# STM32F103CBT6-sphbot.net
KiCad netlist of a schematic drawn in Altium Designer
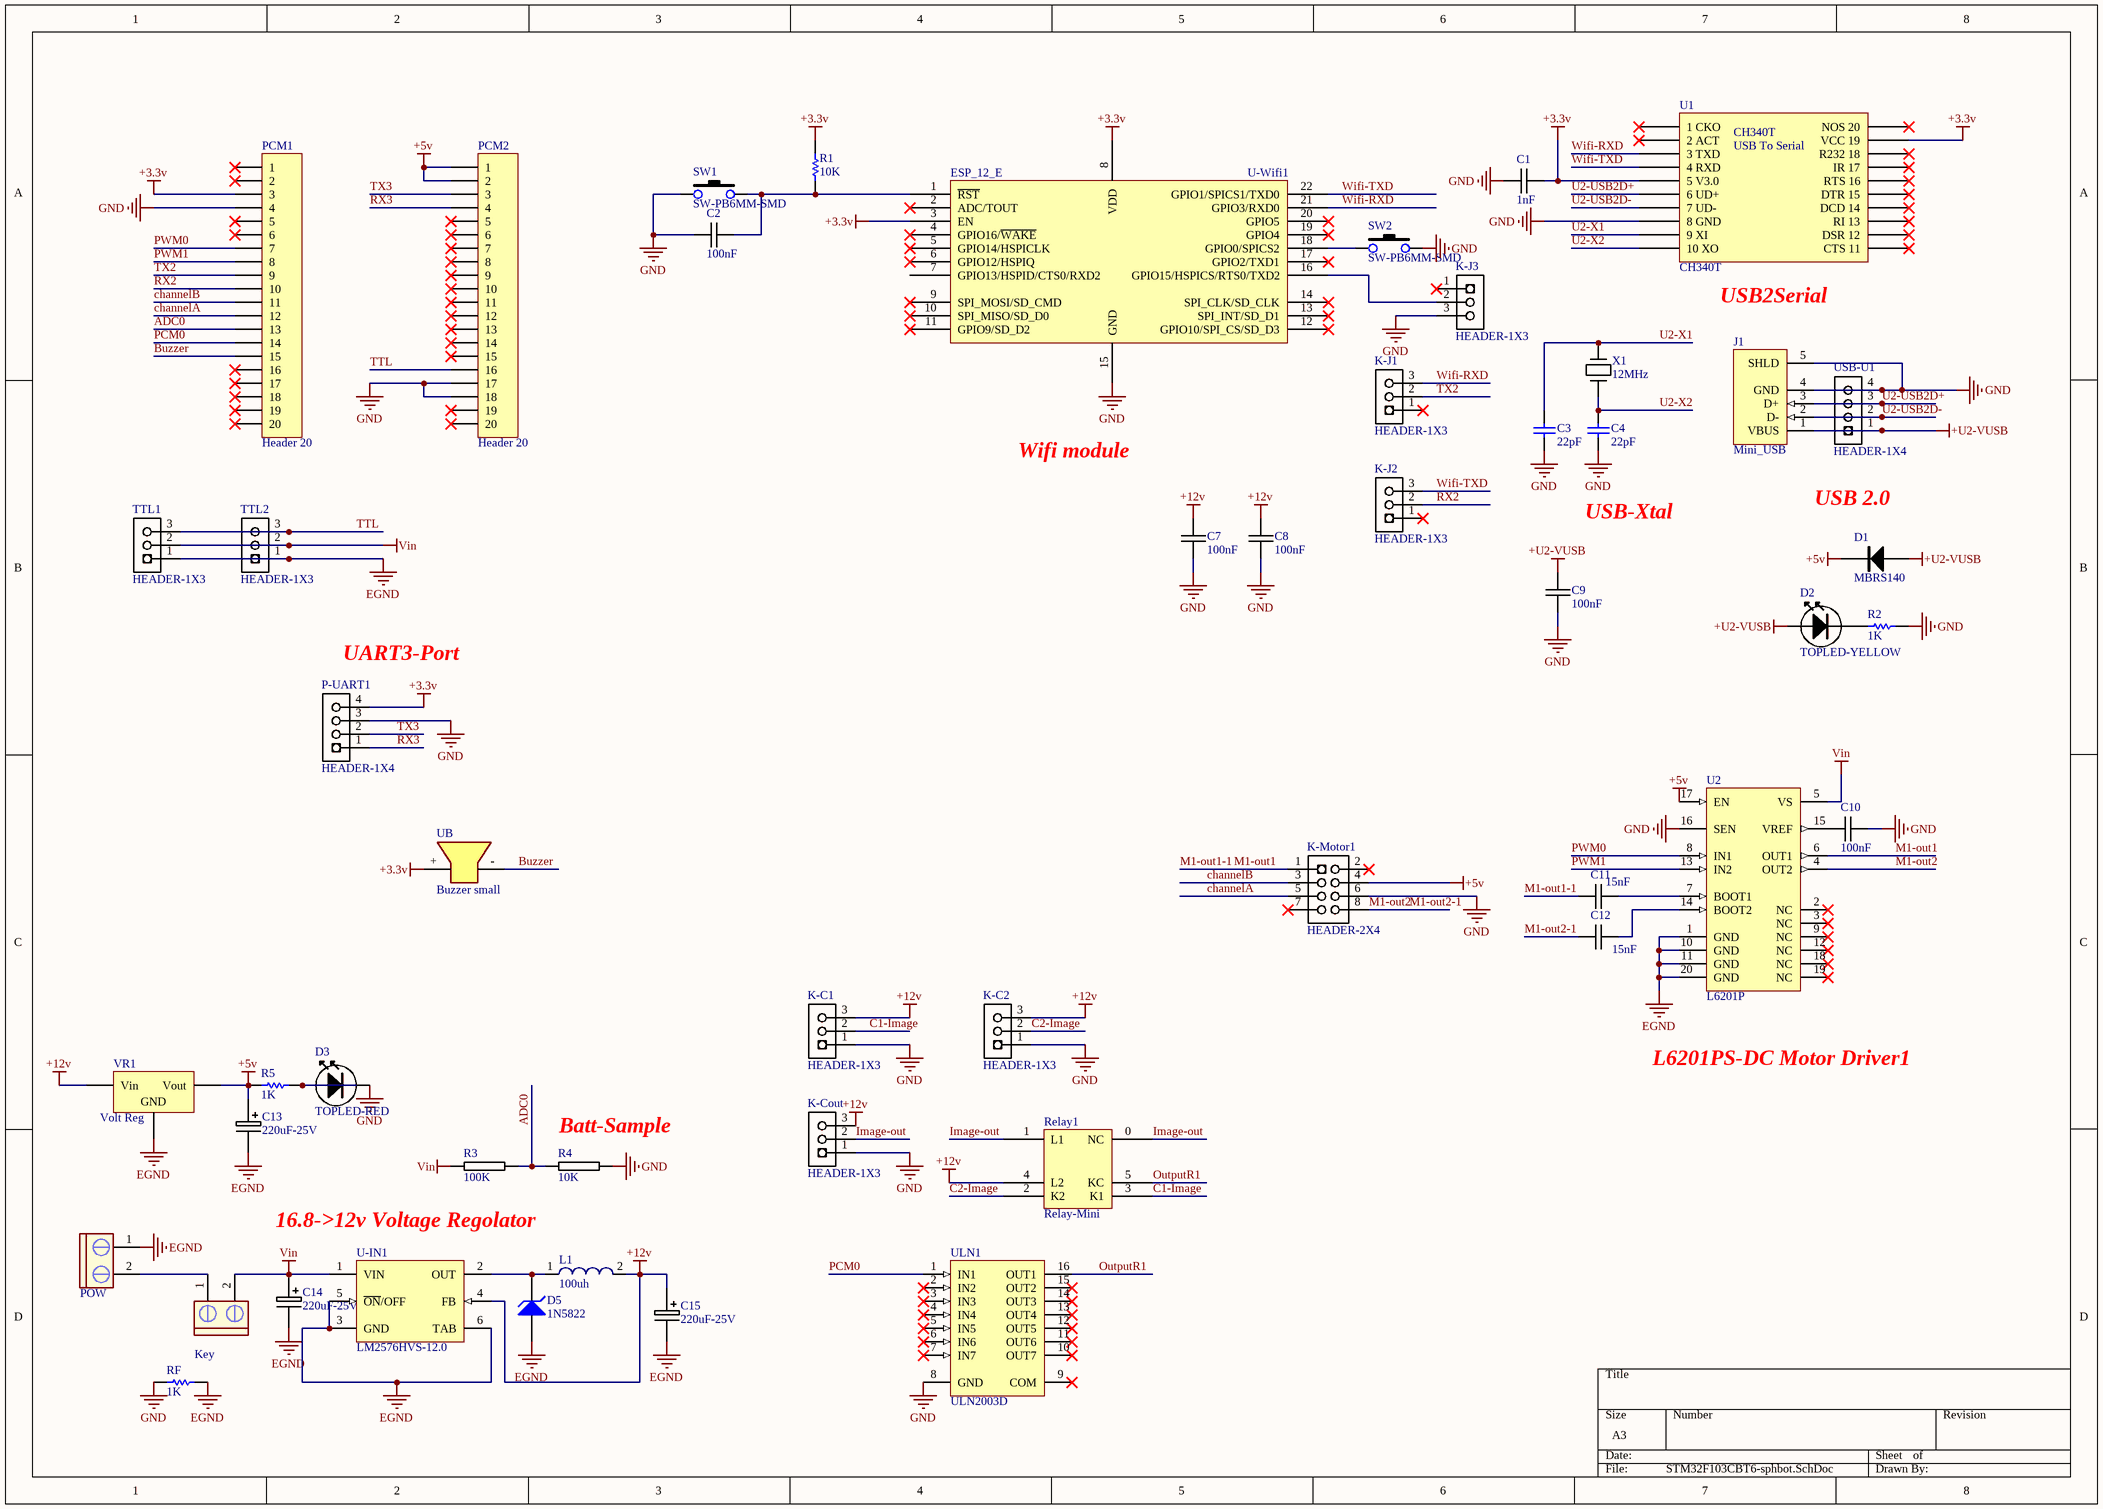
[diagram p0: STM32F103CBT6-sphbot.SchDoc]

(export (version "E")
  (design (tool "Eeschema 10.0.6"))
  (components
    (comp (ref "C1")
      (value "1nF")
      (footprint "0805C-TBD")
      (description "CAPACITOR 0805 CERAMIC")
      (libsource (lib "vh_altium_library") (part "0805C-18PF-50V-C0G-JOH"))
    )
    (comp (ref "C2")
      (value "100nF")
      (footprint "0805C-TBD")
      (description "CAPACITOR 0805 CERAMIC")
      (libsource (lib "vh_altium_library") (part "0805C-100nF-25V-X7R-MUR"))
    )
    (comp (ref "C3")
      (value "22pF")
      (footprint "0805C-TBD")
      (description "Capacitor (Semiconductor SIM Model)")
      (fields (field (name "PUBLISHER") "Altium Limited"))
      (libsource (lib "Miscellaneous Devices") (part "Cap Semi"))
    )
    (comp (ref "C4")
      (value "22pF")
      (footprint "0805C-TBD")
      (description "Capacitor (Semiconductor SIM Model)")
      (fields (field (name "PUBLISHER") "Altium Limited"))
      (libsource (lib "Miscellaneous Devices") (part "Cap Semi"))
    )
    (comp (ref "C7")
      (value "100nF")
      (footprint "0805C-TBD")
      (description "CAPACITOR 0805 CERAMIC")
      (libsource (lib "vh_altium_library") (part "0805C-100nF-25V-X7R-MUR"))
    )
    (comp (ref "C8")
      (value "100nF")
      (footprint "0805C-TBD")
      (description "CAPACITOR 0805 CERAMIC")
      (libsource (lib "vh_altium_library") (part "0805C-100nF-25V-X7R-MUR"))
    )
    (comp (ref "C9")
      (value "100nF")
      (footprint "0805C-TBD")
      (description "CAPACITOR 0805 CERAMIC")
      (libsource (lib "vh_altium_library") (part "0805C-100nF-25V-X7R-MUR"))
    )
    (comp (ref "C10")
      (value "100nF")
      (footprint "0805C-TBD")
      (description "CAPACITOR 0805 CERAMIC")
      (libsource (lib "vh_altium_library") (part "0805C-100nF-25V-X7R-MUR"))
    )
    (comp (ref "C11")
      (value "15nF")
      (footprint "0805C-TBD")
      (description "CAPACITOR 0805 CERAMIC")
      (libsource (lib "vh_altium_library") (part "0805C-100nF-25V-X7R-MUR"))
    )
    (comp (ref "C12")
      (value "15nF")
      (footprint "0805C-TBD")
      (description "CAPACITOR 0805 CERAMIC")
      (libsource (lib "vh_altium_library") (part "0805C-100nF-25V-X7R-MUR"))
    )
    (comp (ref "C13")
      (value "220uF-25V")
      (footprint "PANACAP-F-GENERIC")
      (description "GENERIC CAPACITOR POLARISED")
      (libsource (lib "vh_altium_library") (part "PANACAP-220UF-25V-FK"))
    )
    (comp (ref "C14")
      (value "220uF-25V")
      (footprint "PANACAP-F-GENERIC")
      (description "GENERIC CAPACITOR POLARISED")
      (libsource (lib "vh_altium_library") (part "PANACAP-220UF-25V-FK"))
    )
    (comp (ref "C15")
      (value "220uF-25V")
      (footprint "PANACAP-F-GENERIC")
      (description "GENERIC CAPACITOR POLARISED")
      (libsource (lib "vh_altium_library") (part "PANACAP-220UF-25V-FK"))
    )
    (comp (ref "D1")
      (value "MBRS140")
      (footprint "DIODE-SMA")
      (description "DIODE")
      (libsource (lib "vh_altium_library") (part "MBRS140"))
    )
    (comp (ref "D2")
      (value "TOPLED-YELLOW")
      (footprint "TOPLED-YELLOW")
      (fields
        (field (name "MANUFACTURER PART NUMBER") "LY T676-S1T1-26-Z")
        (field (name "MANUFACTURER") "OSRAM Opto Semiconductors Inc")
      )
      (libsource (lib "vh_altium_library") (part "TOPLED-YELLOW"))
    )
    (comp (ref "D3")
      (value "TOPLED-RED")
      (footprint "TOPLED-RED")
      (description "TOPLED-BLUE")
      (fields
        (field (name "MANUFACTURER") "Kingbright Corp")
        (field (name "MANUFACTURER PART NUMBER") "AA3528APBC/A")
      )
      (libsource (lib "vh_altium_library") (part "TOPLED-BLUE"))
    )
    (comp (ref "D5")
      (value "1N5822")
      (footprint "MELF")
      (description "High-Voltage Power Zener Diode")
      (fields (field (name "PUBLISHER") "Altium Limited"))
      (libsource (lib "Vishay Lite-On Discrete Diode") (part "ZMU100"))
    )
    (comp (ref "J1")
      (value "Mini_USB")
      (footprint "My_USB")
      (description "USB 2.0, Right Angle, SMT, B Type, Receptacle, 5 Position, Black")
      (fields (field (name "PUBLISHER") "Altium Limited"))
      (libsource (lib "Mylib") (part "Mini_USB"))
    )
    (comp (ref "K-C1")
      (value "HEADER-1X3")
      (footprint "HEADER-1X3")
      (libsource (lib "vh_altium_library") (part "HEADER-1X3"))
    )
    (comp (ref "K-C2")
      (value "HEADER-1X3")
      (footprint "HEADER-1X3")
      (libsource (lib "vh_altium_library") (part "HEADER-1X3"))
    )
    (comp (ref "K-Cout")
      (value "HEADER-1X3")
      (footprint "HEADER-1X3")
      (libsource (lib "vh_altium_library") (part "HEADER-1X3"))
    )
    (comp (ref "K-J1")
      (value "HEADER-1X3")
      (footprint "HEADER-1X3")
      (libsource (lib "vh_altium_library") (part "HEADER-1X3"))
    )
    (comp (ref "K-J2")
      (value "HEADER-1X3")
      (footprint "HEADER-1X3")
      (libsource (lib "vh_altium_library") (part "HEADER-1X3"))
    )
    (comp (ref "K-J3")
      (value "HEADER-1X3")
      (footprint "HEADER-1X3")
      (libsource (lib "vh_altium_library") (part "HEADER-1X3"))
    )
    (comp (ref "K-Motor1")
      (value "HEADER-2X4")
      (footprint "HEADER-2X4")
      (libsource (lib "vh_altium_library") (part "HEADER-2X4"))
    )
    (comp (ref "Key")
      (value "CON2 pin blue")
      (footprint "My_CN2")
      (description "Connector blue screw")
      (libsource (lib "Mylib") (part "CON2 pin blue"))
    )
    (comp (ref "L1")
      (value "100uh")
      (footprint "WE-PD 1280")
      (description "SMD-Shielded Power Inductor WE-PD, L=22.0 µH")
      (fields
        (field (name "PARTNO") "744770122")
        (field (name "MANUFACTURER") "Würth Elektronik eiSos GmbH")
        (field (name "CREATED BY") "Christin Zierenner")
      )
      (libsource (lib "WE-PD_rev15b") (part "WE-PD 1280, XL, 744770122"))
    )
    (comp (ref "P-UART1")
      (value "HEADER-1X4")
      (footprint "HEADER-1X4")
      (libsource (lib "vh_altium_library") (part "HEADER-1X4"))
    )
    (comp (ref "PCM1")
      (value "Header 20")
      (footprint "HDR1X20")
      (description "Header, 20-Pin")
      (fields (field (name "PUBLISHER") "Altium Limited"))
      (libsource (lib "Miscellaneous Connectors") (part "Header 20"))
    )
    (comp (ref "PCM2")
      (value "Header 20")
      (footprint "HDR1X20")
      (description "Header, 20-Pin")
      (fields (field (name "PUBLISHER") "Altium Limited"))
      (libsource (lib "Miscellaneous Connectors") (part "Header 20"))
    )
    (comp (ref "POW")
      (value "CON2 pin blue")
      (footprint "My_CN2")
      (description "Connector blue screw")
      (libsource (lib "") (part "CON2 pin blue_1"))
    )
    (comp (ref "R1")
      (value "10K")
      (footprint "0805R-1K")
      (fields (field (name "PUBLISHER") "Altium Limited"))
      (libsource (lib "Panasonic Resistor") (part "ERJ6RS"))
    )
    (comp (ref "R2")
      (value "1K")
      (footprint "0805R-1K")
      (description "Semiconductor Resistor")
      (fields (field (name "PUBLISHER") "Altium Limited"))
      (libsource (lib "Miscellaneous Devices") (part "Res Semi"))
    )
    (comp (ref "R3")
      (value "100K")
      (footprint "0805R-100K")
      (description "RESISTOR 0805 1/4 WATT THIN FILM")
      (libsource (lib "vh_altium_library") (part "0805R-100K"))
    )
    (comp (ref "R4")
      (value "10K")
      (footprint "0805R-10K")
      (description "RESISTOR 0805 1/4 WATT THIN FILM")
      (libsource (lib "vh_altium_library") (part "0805R-10K"))
    )
    (comp (ref "R5")
      (value "1K")
      (footprint "0805R-1K")
      (fields (field (name "PUBLISHER") "Altium Limited"))
      (libsource (lib "Panasonic Resistor") (part "ERJ6RS"))
    )
    (comp (ref "Relay1")
      (value "Relay-Mini")
      (footprint "Relay_Mini")
      (libsource (lib "A2-Elecat") (part "Relay-Mini"))
    )
    (comp (ref "RF")
      (value "1K")
      (footprint "0805R-1K")
      (fields (field (name "PUBLISHER") "Altium Limited"))
      (libsource (lib "Panasonic Resistor") (part "ERJ6RS"))
    )
    (comp (ref "SW1")
      (value "SW-PB6MM-SMD")
      (footprint "SW-PB-SMD")
      (description "PUSHBUTTON SWITCH 6MM SMD")
      (libsource (lib "vh_altium_library") (part "SW-PB6MM-SMD"))
    )
    (comp (ref "SW2")
      (value "SW-PB6MM-SMD")
      (footprint "SW-PB-SMD")
      (description "PUSHBUTTON SWITCH 6MM SMD")
      (libsource (lib "vh_altium_library") (part "SW-PB6MM-SMD"))
    )
    (comp (ref "TTL1")
      (value "HEADER-1X3")
      (footprint "HEADER-1X3")
      (libsource (lib "vh_altium_library") (part "HEADER-1X3"))
    )
    (comp (ref "TTL2")
      (value "HEADER-1X3")
      (footprint "HEADER-1X3")
      (libsource (lib "vh_altium_library") (part "HEADER-1X3"))
    )
    (comp (ref "U-IN1")
      (value "LM2576HVS-12.0")
      (footprint "TS5B_N")
      (description "SIMPLE SWITCHER; 3A Step-Down Voltage Regulator")
      (fields
        (field (name "PARTNUMBER") "LM2576HVS-5.0")
        (field (name "MANUFACTURER") "National Semiconductor")
        (field (name "PUBLISHER") "Altium Limited")
      )
      (libsource (lib "NSC Switcher") (part "LM2576HVS-5.0"))
    )
    (comp (ref "U-Wifi1")
      (value "ESP_12_E")
      (footprint "ESP_12_E")
      (description "ESP-12 Wi-Fi Module by AI-Thinker")
      (libsource (lib "ESP-12") (part "ESP_12_E"))
    )
    (comp (ref "U1")
      (value "CH340T")
      (footprint "TSSOP20")
      (libsource (lib "MK-Integrated_Library") (part "CH340T"))
    )
    (comp (ref "U2")
      (value "L6201P")
      (footprint "PowerSO20_N")
      (description "DMOS Full Bridge Driver")
      (fields (field (name "PUBLISHER") "Altium Limited"))
      (libsource (lib "ST Interface DC Motor Controller") (part "L6201P"))
    )
    (comp (ref "UB")
      (value "Buzzer small")
      (footprint "My_Buzzer")
      (description "5-12v small buzzer (12mm)")
      (libsource (lib "Mylib") (part "Buzzer"))
    )
    (comp (ref "ULN1")
      (value "ULN2003D")
      (footprint "SO16_N")
      (description "Seven Darlington Array")
      (fields (field (name "PUBLISHER") "Altium Limited"))
      (libsource (lib "ST Interface Darlington Driver") (part "ULN2002D"))
    )
    (comp (ref "USB-U1")
      (value "HEADER-1X4")
      (footprint "HEADER-1X4")
      (libsource (lib "vh_altium_library") (part "HEADER-1X4"))
    )
    (comp (ref "VR1")
      (value "Volt Reg")
      (footprint "D2PAK")
      (description "Voltage Regulator")
      (fields (field (name "PUBLISHER") "Altium Limited"))
      (libsource (lib "Miscellaneous Devices") (part "Volt Reg"))
    )
    (comp (ref "X1")
      (value "12MHz")
      (footprint "XTAL-RU49/4")
      (description "GENERIC CRYSTAL")
      (libsource (lib "vh_altium_library") (part "CRYSTAL-GENERIC"))
    )
  )
  (nets
    (net (code "1") (name "+3.3v") (class "Default")
      (node (ref "C1") (pin "1") (pintype "passive"))
      (node (ref "P-UART1") (pin "4") (pintype "passive"))
      (node (ref "PCM1") (pin "3") (pinfunction "3_3") (pintype "passive"))
      (node (ref "R1") (pin "2") (pinfunction "2_2") (pintype "passive"))
      (node (ref "U-Wifi1") (pin "3") (pinfunction "EN_3") (pintype "passive"))
      (node (ref "U-Wifi1") (pin "8") (pinfunction "VDD_8") (pintype "passive"))
      (node (ref "U1") (pin "19") (pinfunction "VCC_19_19") (pintype "passive"))
      (node (ref "U1") (pin "5") (pinfunction "5_V3.0_5") (pintype "passive"))
      (node (ref "UB") (pin "+") (pinfunction "1_+") (pintype "power_in"))
    )
    (net (code "2") (name "+5v") (class "Default")
      (node (ref "C13") (pin "+") (pinfunction "+_+") (pintype "passive"))
      (node (ref "D1") (pin "K") (pinfunction "K_K") (pintype "passive"))
      (node (ref "K-Motor1") (pin "4") (pintype "passive"))
      (node (ref "PCM2") (pin "1") (pinfunction "1_1") (pintype "passive"))
      (node (ref "PCM2") (pin "2") (pinfunction "2_2") (pintype "passive"))
      (node (ref "R5") (pin "2") (pinfunction "2_2") (pintype "passive"))
      (node (ref "U2") (pin "17") (pinfunction "EN_17") (pintype "input"))
      (node (ref "VR1") (pin "3") (pinfunction "Vout_3") (pintype "passive"))
    )
    (net (code "3") (name "+12v") (class "Default")
      (node (ref "C15") (pin "+") (pinfunction "+_+") (pintype "passive"))
      (node (ref "C7") (pin "1") (pintype "passive"))
      (node (ref "C8") (pin "1") (pintype "passive"))
      (node (ref "K-C1") (pin "3") (pintype "passive"))
      (node (ref "K-C2") (pin "3") (pintype "passive"))
      (node (ref "K-Cout") (pin "3") (pintype "passive"))
      (node (ref "L1") (pin "2") (pinfunction "2_2") (pintype "passive"))
      (node (ref "Relay1") (pin "4") (pinfunction "L2_4") (pintype "passive"))
      (node (ref "U-IN1") (pin "4") (pinfunction "FB_4") (pintype "input"))
      (node (ref "VR1") (pin "1") (pinfunction "Vin_1") (pintype "passive"))
    )
    (net (code "4") (name "+U2-VUSB") (class "Default")
      (node (ref "C9") (pin "1") (pintype "passive"))
      (node (ref "D1") (pin "A") (pinfunction "A_A") (pintype "passive"))
      (node (ref "D2") (pin "A") (pintype "passive"))
      (node (ref "J1") (pin "1") (pinfunction "VBUS_1") (pintype "power_in"))
      (node (ref "USB-U1") (pin "1") (pintype "passive"))
    )
    (net (code "5") (name "/ADC0") (class "Default")
      (node (ref "PCM1") (pin "13") (pinfunction "13_13") (pintype "passive"))
      (node (ref "R3") (pin "2") (pintype "passive"))
      (node (ref "R4") (pin "1") (pintype "passive"))
    )
    (net (code "6") (name "/Buzzer") (class "Default")
      (node (ref "PCM1") (pin "15") (pinfunction "15_15") (pintype "passive"))
      (node (ref "UB") (pin "-") (pinfunction "2_-") (pintype "power_in"))
    )
    (net (code "7") (name "/C1-Image") (class "Default")
      (node (ref "K-C1") (pin "2") (pintype "passive"))
      (node (ref "Relay1") (pin "3") (pinfunction "K1_3") (pintype "passive"))
    )
    (net (code "8") (name "/C2-Image") (class "Default")
      (node (ref "K-C2") (pin "2") (pintype "passive"))
      (node (ref "Relay1") (pin "2") (pinfunction "K2_2") (pintype "passive"))
    )
    (net (code "9") (name "/Image-out") (class "Default")
      (node (ref "K-Cout") (pin "2") (pintype "passive"))
      (node (ref "Relay1") (pin "0") (pinfunction "NC_0") (pintype "passive"))
      (node (ref "Relay1") (pin "1") (pinfunction "L1_1") (pintype "passive"))
    )
    (net (code "10") (name "/M1-out1") (class "Default")
      (node (ref "C11") (pin "1") (pintype "passive"))
      (node (ref "K-Motor1") (pin "1") (pintype "passive"))
      (node (ref "U2") (pin "6") (pinfunction "OUT1_6") (pintype "output"))
    )
    (net (code "11") (name "/M1-out2") (class "Default")
      (node (ref "C12") (pin "1") (pintype "passive"))
      (node (ref "K-Motor1") (pin "8") (pintype "passive"))
      (node (ref "U2") (pin "4") (pinfunction "OUT2_4") (pintype "output"))
    )
    (net (code "12") (name "/OutputR1") (class "Default")
      (node (ref "Relay1") (pin "5") (pinfunction "KC_5") (pintype "passive"))
      (node (ref "ULN1") (pin "16") (pinfunction "OUT1_16") (pintype "open_collector"))
    )
    (net (code "13") (name "/PCM0") (class "Default")
      (node (ref "PCM1") (pin "14") (pinfunction "14_14") (pintype "passive"))
      (node (ref "ULN1") (pin "1") (pinfunction "IN1_1") (pintype "input"))
    )
    (net (code "14") (name "/PWM0") (class "Default")
      (node (ref "PCM1") (pin "7") (pinfunction "7_7") (pintype "passive"))
      (node (ref "U2") (pin "8") (pinfunction "IN1_8") (pintype "input"))
    )
    (net (code "15") (name "/PWM1") (class "Default")
      (node (ref "PCM1") (pin "8") (pinfunction "8_8") (pintype "passive"))
      (node (ref "U2") (pin "13") (pinfunction "IN2_13") (pintype "input"))
    )
    (net (code "16") (name "/RX2") (class "Default")
      (node (ref "K-J2") (pin "2") (pintype "passive"))
      (node (ref "PCM1") (pin "10") (pinfunction "10_10") (pintype "passive"))
    )
    (net (code "17") (name "/RX3") (class "Default")
      (node (ref "P-UART1") (pin "1") (pintype "passive"))
      (node (ref "PCM2") (pin "4") (pinfunction "4_4") (pintype "passive"))
    )
    (net (code "18") (name "/TTL") (class "Default")
      (node (ref "PCM2") (pin "16") (pinfunction "16_16") (pintype "passive"))
      (node (ref "TTL1") (pin "3") (pintype "passive"))
      (node (ref "TTL2") (pin "3") (pintype "passive"))
    )
    (net (code "19") (name "/TX2") (class "Default")
      (node (ref "K-J1") (pin "2") (pintype "passive"))
      (node (ref "PCM1") (pin "9") (pinfunction "9_9") (pintype "passive"))
    )
    (net (code "20") (name "/TX3") (class "Default")
      (node (ref "P-UART1") (pin "2") (pintype "passive"))
      (node (ref "PCM2") (pin "3") (pinfunction "3_3") (pintype "passive"))
    )
    (net (code "21") (name "/U2-USB2D+") (class "Default")
      (node (ref "J1") (pin "3") (pinfunction "D+_3") (pintype "input"))
      (node (ref "U1") (pin "6") (pinfunction "6_UD+_6") (pintype "passive"))
      (node (ref "USB-U1") (pin "3") (pintype "passive"))
    )
    (net (code "22") (name "/U2-USB2D-") (class "Default")
      (node (ref "J1") (pin "2") (pinfunction "D-_2") (pintype "input"))
      (node (ref "U1") (pin "7") (pinfunction "7_UD-_7") (pintype "passive"))
      (node (ref "USB-U1") (pin "2") (pintype "passive"))
    )
    (net (code "23") (name "/U2-X1") (class "Default")
      (node (ref "C3") (pin "2") (pinfunction "2_2") (pintype "passive"))
      (node (ref "U1") (pin "9") (pinfunction "9_XI_9") (pintype "passive"))
      (node (ref "X1") (pin "1") (pintype "passive"))
    )
    (net (code "24") (name "/U2-X2") (class "Default")
      (node (ref "C4") (pin "2") (pinfunction "2_2") (pintype "passive"))
      (node (ref "U1") (pin "10") (pinfunction "10_XO_10") (pintype "passive"))
      (node (ref "X1") (pin "2") (pintype "passive"))
    )
    (net (code "25") (name "/Wifi-RXD") (class "Default")
      (node (ref "K-J1") (pin "3") (pintype "passive"))
      (node (ref "U-Wifi1") (pin "21") (pinfunction "GPIO3/RXD0_21") (pintype "passive"))
      (node (ref "U1") (pin "3") (pinfunction "3_TXD_3") (pintype "passive"))
    )
    (net (code "26") (name "/Wifi-TXD") (class "Default")
      (node (ref "K-J2") (pin "3") (pintype "passive"))
      (node (ref "U-Wifi1") (pin "22") (pinfunction "GPIO1/SPICS1/TXD0_22") (pintype "passive"))
      (node (ref "U1") (pin "4") (pinfunction "4_RXD_4") (pintype "passive"))
    )
    (net (code "27") (name "/channelA") (class "Default")
      (node (ref "K-Motor1") (pin "5") (pintype "passive"))
      (node (ref "PCM1") (pin "12") (pinfunction "12_12") (pintype "passive"))
    )
    (net (code "28") (name "/channelB") (class "Default")
      (node (ref "K-Motor1") (pin "3") (pintype "passive"))
      (node (ref "PCM1") (pin "11") (pinfunction "11_11") (pintype "passive"))
    )
    (net (code "29") (name "EGND") (class "Default")
      (node (ref "C13") (pin "-") (pinfunction "-_-") (pintype "passive"))
      (node (ref "C14") (pin "-") (pinfunction "-_-") (pintype "passive"))
      (node (ref "C15") (pin "-") (pinfunction "-_-") (pintype "passive"))
      (node (ref "D5") (pin "1") (pinfunction "A_1") (pintype "passive"))
      (node (ref "POW") (pin "1") (pinfunction "1_1") (pintype "passive"))
      (node (ref "RF") (pin "1") (pinfunction "1_1") (pintype "passive"))
      (node (ref "TTL1") (pin "1") (pintype "passive"))
      (node (ref "TTL2") (pin "1") (pintype "passive"))
      (node (ref "U-IN1") (pin "3") (pinfunction "GND_3") (pintype "power_in"))
      (node (ref "U-IN1") (pin "5") (pinfunction "~{ON}/OFF_5") (pintype "input"))
      (node (ref "U-IN1") (pin "6") (pinfunction "TAB_6") (pintype "power_in"))
      (node (ref "U2") (pin "1") (pinfunction "GND_1") (pintype "power_in"))
      (node (ref "U2") (pin "10") (pinfunction "GND_10") (pintype "power_in"))
      (node (ref "U2") (pin "11") (pinfunction "GND_11") (pintype "power_in"))
      (node (ref "U2") (pin "20") (pinfunction "GND_20") (pintype "power_in"))
      (node (ref "VR1") (pin "2") (pinfunction "GND_2") (pintype "passive"))
    )
    (net (code "30") (name "GND") (class "Default")
      (node (ref "C1") (pin "2") (pintype "passive"))
      (node (ref "C10") (pin "2") (pintype "passive"))
      (node (ref "C2") (pin "2") (pintype "passive"))
      (node (ref "C3") (pin "1") (pinfunction "1_1") (pintype "passive"))
      (node (ref "C4") (pin "1") (pinfunction "1_1") (pintype "passive"))
      (node (ref "C7") (pin "2") (pintype "passive"))
      (node (ref "C8") (pin "2") (pintype "passive"))
      (node (ref "C9") (pin "2") (pintype "passive"))
      (node (ref "D3") (pin "K") (pintype "passive"))
      (node (ref "J1") (pin "4") (pinfunction "GND_4") (pintype "power_in"))
      (node (ref "J1") (pin "5") (pinfunction "SHLD_5") (pintype "passive"))
      (node (ref "K-C1") (pin "1") (pintype "passive"))
      (node (ref "K-C2") (pin "1") (pintype "passive"))
      (node (ref "K-Cout") (pin "1") (pintype "passive"))
      (node (ref "K-J3") (pin "3") (pintype "passive"))
      (node (ref "K-Motor1") (pin "6") (pintype "passive"))
      (node (ref "P-UART1") (pin "3") (pintype "passive"))
      (node (ref "PCM1") (pin "4") (pinfunction "4_4") (pintype "passive"))
      (node (ref "PCM2") (pin "17") (pinfunction "17_17") (pintype "passive"))
      (node (ref "PCM2") (pin "18") (pinfunction "18_18") (pintype "passive"))
      (node (ref "R2") (pin "1") (pinfunction "1_1") (pintype "passive"))
      (node (ref "R4") (pin "2") (pintype "passive"))
      (node (ref "RF") (pin "2") (pinfunction "2_2") (pintype "passive"))
      (node (ref "SW1") (pin "1") (pintype "passive"))
      (node (ref "SW2") (pin "2") (pintype "passive"))
      (node (ref "U-Wifi1") (pin "15") (pinfunction "GND_15") (pintype "passive"))
      (node (ref "U1") (pin "8") (pinfunction "8_GND_8") (pintype "passive"))
      (node (ref "U2") (pin "16") (pinfunction "SEN_16") (pintype "passive"))
      (node (ref "ULN1") (pin "8") (pinfunction "GND_8") (pintype "power_in"))
      (node (ref "USB-U1") (pin "4") (pintype "passive"))
    )
    (net (code "31") (name "Net-(D2-PadK)") (class "Default")
      (node (ref "D2") (pin "K") (pintype "passive"))
      (node (ref "R2") (pin "2") (pinfunction "2_2") (pintype "passive"))
    )
    (net (code "32") (name "Net-(D3-PadA)") (class "Default")
      (node (ref "D3") (pin "A") (pintype "passive"))
      (node (ref "R5") (pin "1") (pinfunction "1_1") (pintype "passive"))
    )
    (net (code "33") (name "Net-(D5-K)") (class "Default")
      (node (ref "D5") (pin "2") (pinfunction "K_2") (pintype "passive"))
      (node (ref "L1") (pin "1") (pinfunction "1_1") (pintype "passive"))
      (node (ref "U-IN1") (pin "2") (pinfunction "OUT_2") (pintype "power_in"))
    )
    (net (code "34") (name "Net-(Key-Pad1)") (class "Default")
      (node (ref "Key") (pin "1") (pinfunction "1_1") (pintype "passive"))
      (node (ref "POW") (pin "2") (pinfunction "2_2") (pintype "passive"))
    )
    (net (code "35") (name "Net-(U-Wifi1-GPIO0{slash}SPICS2)") (class "Default")
      (node (ref "SW2") (pin "1") (pintype "passive"))
      (node (ref "U-Wifi1") (pin "18") (pinfunction "GPIO0/SPICS2_18") (pintype "passive"))
    )
    (net (code "36") (name "Net-(U-Wifi1-GPIO15{slash}HSPICS{slash}RTS0{slash}TXD2)") (class "Default")
      (node (ref "K-J3") (pin "2") (pintype "passive"))
      (node (ref "U-Wifi1") (pin "16") (pinfunction "GPIO15/HSPICS/RTS0/TXD2_16") (pintype "passive"))
    )
    (net (code "37") (name "Net-(U-Wifi1-~{RST})") (class "Default")
      (node (ref "C2") (pin "1") (pintype "passive"))
      (node (ref "R1") (pin "1") (pinfunction "1_1") (pintype "passive"))
      (node (ref "SW1") (pin "2") (pintype "passive"))
      (node (ref "U-Wifi1") (pin "1") (pinfunction "~{RST}_1") (pintype "passive"))
    )
    (net (code "38") (name "Net-(U2-BOOT1)") (class "Default")
      (node (ref "C11") (pin "2") (pintype "passive"))
      (node (ref "U2") (pin "7") (pinfunction "BOOT1_7") (pintype "input"))
    )
    (net (code "39") (name "Net-(U2-BOOT2)") (class "Default")
      (node (ref "C12") (pin "2") (pintype "passive"))
      (node (ref "U2") (pin "14") (pinfunction "BOOT2_14") (pintype "input"))
    )
    (net (code "40") (name "Net-(U2-VREF)") (class "Default")
      (node (ref "C10") (pin "1") (pintype "passive"))
      (node (ref "U2") (pin "15") (pinfunction "VREF_15") (pintype "output"))
    )
    (net (code "41") (name "Vin") (class "Default")
      (node (ref "C14") (pin "+") (pinfunction "+_+") (pintype "passive"))
      (node (ref "Key") (pin "2") (pinfunction "2_2") (pintype "passive"))
      (node (ref "R3") (pin "1") (pintype "passive"))
      (node (ref "TTL1") (pin "2") (pintype "passive"))
      (node (ref "TTL2") (pin "2") (pintype "passive"))
      (node (ref "U-IN1") (pin "1") (pinfunction "VIN_1") (pintype "power_in"))
      (node (ref "U2") (pin "5") (pinfunction "VS_5") (pintype "power_in"))
    )
    (net (code "42") (name "unconnected-(K-J1-Pad1)") (class "Default")
      (node (ref "K-J1") (pin "1") (pintype "passive+no_connect"))
    )
    (net (code "43") (name "unconnected-(K-J2-Pad1)") (class "Default")
      (node (ref "K-J2") (pin "1") (pintype "passive+no_connect"))
    )
    (net (code "44") (name "unconnected-(K-J3-Pad1)") (class "Default")
      (node (ref "K-J3") (pin "1") (pintype "passive+no_connect"))
    )
    (net (code "45") (name "unconnected-(K-Motor1-Pad2)") (class "Default")
      (node (ref "K-Motor1") (pin "2") (pintype "passive+no_connect"))
    )
    (net (code "46") (name "unconnected-(K-Motor1-Pad7)") (class "Default")
      (node (ref "K-Motor1") (pin "7") (pintype "passive+no_connect"))
    )
    (net (code "47") (name "unconnected-(PCM1-Pad1)") (class "Default")
      (node (ref "PCM1") (pin "1") (pinfunction "1_1") (pintype "passive+no_connect"))
    )
    (net (code "48") (name "unconnected-(PCM1-Pad2)") (class "Default")
      (node (ref "PCM1") (pin "2") (pinfunction "2_2") (pintype "passive+no_connect"))
    )
    (net (code "49") (name "unconnected-(PCM1-Pad5)") (class "Default")
      (node (ref "PCM1") (pin "5") (pinfunction "5_5") (pintype "passive+no_connect"))
    )
    (net (code "50") (name "unconnected-(PCM1-Pad6)") (class "Default")
      (node (ref "PCM1") (pin "6") (pinfunction "6_6") (pintype "passive+no_connect"))
    )
    (net (code "51") (name "unconnected-(PCM1-Pad16)") (class "Default")
      (node (ref "PCM1") (pin "16") (pinfunction "16_16") (pintype "passive+no_connect"))
    )
    (net (code "52") (name "unconnected-(PCM1-Pad17)") (class "Default")
      (node (ref "PCM1") (pin "17") (pinfunction "17_17") (pintype "passive+no_connect"))
    )
    (net (code "53") (name "unconnected-(PCM1-Pad18)") (class "Default")
      (node (ref "PCM1") (pin "18") (pinfunction "18_18") (pintype "passive+no_connect"))
    )
    (net (code "54") (name "unconnected-(PCM1-Pad19)") (class "Default")
      (node (ref "PCM1") (pin "19") (pinfunction "19_19") (pintype "passive+no_connect"))
    )
    (net (code "55") (name "unconnected-(PCM1-Pad20)") (class "Default")
      (node (ref "PCM1") (pin "20") (pinfunction "20_20") (pintype "passive+no_connect"))
    )
    (net (code "56") (name "unconnected-(PCM2-Pad5)") (class "Default")
      (node (ref "PCM2") (pin "5") (pinfunction "5_5") (pintype "passive+no_connect"))
    )
    (net (code "57") (name "unconnected-(PCM2-Pad6)") (class "Default")
      (node (ref "PCM2") (pin "6") (pinfunction "6_6") (pintype "passive+no_connect"))
    )
    (net (code "58") (name "unconnected-(PCM2-Pad7)") (class "Default")
      (node (ref "PCM2") (pin "7") (pinfunction "7_7") (pintype "passive+no_connect"))
    )
    (net (code "59") (name "unconnected-(PCM2-Pad8)") (class "Default")
      (node (ref "PCM2") (pin "8") (pinfunction "8_8") (pintype "passive+no_connect"))
    )
    (net (code "60") (name "unconnected-(PCM2-Pad9)") (class "Default")
      (node (ref "PCM2") (pin "9") (pinfunction "9_9") (pintype "passive+no_connect"))
    )
    (net (code "61") (name "unconnected-(PCM2-Pad10)") (class "Default")
      (node (ref "PCM2") (pin "10") (pinfunction "10_10") (pintype "passive+no_connect"))
    )
    (net (code "62") (name "unconnected-(PCM2-Pad11)") (class "Default")
      (node (ref "PCM2") (pin "11") (pinfunction "11_11") (pintype "passive+no_connect"))
    )
    (net (code "63") (name "unconnected-(PCM2-Pad12)") (class "Default")
      (node (ref "PCM2") (pin "12") (pinfunction "12_12") (pintype "passive+no_connect"))
    )
    (net (code "64") (name "unconnected-(PCM2-Pad13)") (class "Default")
      (node (ref "PCM2") (pin "13") (pinfunction "13_13") (pintype "passive+no_connect"))
    )
    (net (code "65") (name "unconnected-(PCM2-Pad14)") (class "Default")
      (node (ref "PCM2") (pin "14") (pinfunction "14_14") (pintype "passive+no_connect"))
    )
    (net (code "66") (name "unconnected-(PCM2-Pad15)") (class "Default")
      (node (ref "PCM2") (pin "15") (pinfunction "15_15") (pintype "passive+no_connect"))
    )
    (net (code "67") (name "unconnected-(PCM2-Pad19)") (class "Default")
      (node (ref "PCM2") (pin "19") (pinfunction "19_19") (pintype "passive+no_connect"))
    )
    (net (code "68") (name "unconnected-(PCM2-Pad20)") (class "Default")
      (node (ref "PCM2") (pin "20") (pinfunction "20_20") (pintype "passive+no_connect"))
    )
    (net (code "69") (name "unconnected-(U-Wifi1-ADC{slash}TOUT-Pad2)") (class "Default")
      (node (ref "U-Wifi1") (pin "2") (pinfunction "ADC/TOUT_2") (pintype "passive+no_connect"))
    )
    (net (code "70") (name "unconnected-(U-Wifi1-GPIO2{slash}TXD1-Pad17)") (class "Default")
      (node (ref "U-Wifi1") (pin "17") (pinfunction "GPIO2/TXD1_17") (pintype "passive+no_connect"))
    )
    (net (code "71") (name "unconnected-(U-Wifi1-GPIO4-Pad19)") (class "Default")
      (node (ref "U-Wifi1") (pin "19") (pinfunction "GPIO4_19") (pintype "passive+no_connect"))
    )
    (net (code "72") (name "unconnected-(U-Wifi1-GPIO5-Pad20)") (class "Default")
      (node (ref "U-Wifi1") (pin "20") (pinfunction "GPIO5_20") (pintype "passive+no_connect"))
    )
    (net (code "73") (name "unconnected-(U-Wifi1-GPIO9{slash}SD_D2-Pad11)") (class "Default")
      (node (ref "U-Wifi1") (pin "11") (pinfunction "GPIO9/SD_D2_11") (pintype "passive+no_connect"))
    )
    (net (code "74") (name "unconnected-(U-Wifi1-GPIO10{slash}SPI_CS{slash}SD_D3-Pad12)") (class "Default")
      (node (ref "U-Wifi1") (pin "12") (pinfunction "GPIO10/SPI_CS/SD_D3_12") (pintype "passive+no_connect"))
    )
    (net (code "75") (name "unconnected-(U-Wifi1-GPIO12{slash}HSPIQ-Pad6)") (class "Default")
      (node (ref "U-Wifi1") (pin "6") (pinfunction "GPIO12/HSPIQ_6") (pintype "passive+no_connect"))
    )
    (net (code "76") (name "unconnected-(U-Wifi1-GPIO13{slash}HSPID{slash}CTS0{slash}RXD2-Pad7)") (class "Default")
      (node (ref "U-Wifi1") (pin "7") (pinfunction "GPIO13/HSPID/CTS0/RXD2_7") (pintype "passive"))
    )
    (net (code "77") (name "unconnected-(U-Wifi1-GPIO14{slash}HSPICLK-Pad5)") (class "Default")
      (node (ref "U-Wifi1") (pin "5") (pinfunction "GPIO14/HSPICLK_5") (pintype "passive+no_connect"))
    )
    (net (code "78") (name "unconnected-(U-Wifi1-GPIO16{slash}~{WAKE}-Pad4)") (class "Default")
      (node (ref "U-Wifi1") (pin "4") (pinfunction "GPIO16/~{WAKE}_4") (pintype "passive+no_connect"))
    )
    (net (code "79") (name "unconnected-(U-Wifi1-SPI_CLK{slash}SD_CLK-Pad14)") (class "Default")
      (node (ref "U-Wifi1") (pin "14") (pinfunction "SPI_CLK/SD_CLK_14") (pintype "passive+no_connect"))
    )
    (net (code "80") (name "unconnected-(U-Wifi1-SPI_INT{slash}SD_D1-Pad13)") (class "Default")
      (node (ref "U-Wifi1") (pin "13") (pinfunction "SPI_INT/SD_D1_13") (pintype "passive+no_connect"))
    )
    (net (code "81") (name "unconnected-(U-Wifi1-SPI_MISO{slash}SD_D0-Pad10)") (class "Default")
      (node (ref "U-Wifi1") (pin "10") (pinfunction "SPI_MISO/SD_D0_10") (pintype "passive+no_connect"))
    )
    (net (code "82") (name "unconnected-(U-Wifi1-SPI_MOSI{slash}SD_CMD-Pad9)") (class "Default")
      (node (ref "U-Wifi1") (pin "9") (pinfunction "SPI_MOSI/SD_CMD_9") (pintype "passive+no_connect"))
    )
    (net (code "83") (name "unconnected-(U1-1_CKO-Pad1)") (class "Default")
      (node (ref "U1") (pin "1") (pinfunction "1_CKO_1") (pintype "passive+no_connect"))
    )
    (net (code "84") (name "unconnected-(U1-2_ACT-Pad2)") (class "Default")
      (node (ref "U1") (pin "2") (pinfunction "2_ACT_2") (pintype "passive+no_connect"))
    )
    (net (code "85") (name "unconnected-(U1-CTS_11-Pad11)") (class "Default")
      (node (ref "U1") (pin "11") (pinfunction "CTS_11_11") (pintype "passive+no_connect"))
    )
    (net (code "86") (name "unconnected-(U1-DCD_14-Pad14)") (class "Default")
      (node (ref "U1") (pin "14") (pinfunction "DCD_14_14") (pintype "passive+no_connect"))
    )
    (net (code "87") (name "unconnected-(U1-DSR_12-Pad12)") (class "Default")
      (node (ref "U1") (pin "12") (pinfunction "DSR_12_12") (pintype "passive+no_connect"))
    )
    (net (code "88") (name "unconnected-(U1-DTR_15-Pad15)") (class "Default")
      (node (ref "U1") (pin "15") (pinfunction "DTR_15_15") (pintype "passive+no_connect"))
    )
    (net (code "89") (name "unconnected-(U1-IR_17-Pad17)") (class "Default")
      (node (ref "U1") (pin "17") (pinfunction "IR_17_17") (pintype "passive+no_connect"))
    )
    (net (code "90") (name "unconnected-(U1-NOS_20-Pad20)") (class "Default")
      (node (ref "U1") (pin "20") (pinfunction "NOS_20_20") (pintype "passive+no_connect"))
    )
    (net (code "91") (name "unconnected-(U1-R232_18-Pad18)") (class "Default")
      (node (ref "U1") (pin "18") (pinfunction "R232_18_18") (pintype "passive+no_connect"))
    )
    (net (code "92") (name "unconnected-(U1-RI_13-Pad13)") (class "Default")
      (node (ref "U1") (pin "13") (pinfunction "RI_13_13") (pintype "passive+no_connect"))
    )
    (net (code "93") (name "unconnected-(U1-RTS_16-Pad16)") (class "Default")
      (node (ref "U1") (pin "16") (pinfunction "RTS_16_16") (pintype "passive+no_connect"))
    )
    (net (code "94") (name "unconnected-(U2-NC-Pad2)") (class "Default")
      (node (ref "U2") (pin "2") (pinfunction "NC_2") (pintype "passive+no_connect"))
    )
    (net (code "95") (name "unconnected-(U2-NC-Pad3)") (class "Default")
      (node (ref "U2") (pin "3") (pinfunction "NC_3") (pintype "passive+no_connect"))
    )
    (net (code "96") (name "unconnected-(U2-NC-Pad9)") (class "Default")
      (node (ref "U2") (pin "9") (pinfunction "NC_9") (pintype "passive+no_connect"))
    )
    (net (code "97") (name "unconnected-(U2-NC-Pad12)") (class "Default")
      (node (ref "U2") (pin "12") (pinfunction "NC_12") (pintype "passive+no_connect"))
    )
    (net (code "98") (name "unconnected-(U2-NC-Pad18)") (class "Default")
      (node (ref "U2") (pin "18") (pinfunction "NC_18") (pintype "passive+no_connect"))
    )
    (net (code "99") (name "unconnected-(U2-NC-Pad19)") (class "Default")
      (node (ref "U2") (pin "19") (pinfunction "NC_19") (pintype "passive+no_connect"))
    )
    (net (code "100") (name "unconnected-(ULN1-COM-Pad9)") (class "Default")
      (node (ref "ULN1") (pin "9") (pinfunction "COM_9") (pintype "passive+no_connect"))
    )
    (net (code "101") (name "unconnected-(ULN1-IN2-Pad2)") (class "Default")
      (node (ref "ULN1") (pin "2") (pinfunction "IN2_2") (pintype "input+no_connect"))
    )
    (net (code "102") (name "unconnected-(ULN1-IN3-Pad3)") (class "Default")
      (node (ref "ULN1") (pin "3") (pinfunction "IN3_3") (pintype "input+no_connect"))
    )
    (net (code "103") (name "unconnected-(ULN1-IN4-Pad4)") (class "Default")
      (node (ref "ULN1") (pin "4") (pinfunction "IN4_4") (pintype "input+no_connect"))
    )
    (net (code "104") (name "unconnected-(ULN1-IN5-Pad5)") (class "Default")
      (node (ref "ULN1") (pin "5") (pinfunction "IN5_5") (pintype "input+no_connect"))
    )
    (net (code "105") (name "unconnected-(ULN1-IN6-Pad6)") (class "Default")
      (node (ref "ULN1") (pin "6") (pinfunction "IN6_6") (pintype "input+no_connect"))
    )
    (net (code "106") (name "unconnected-(ULN1-IN7-Pad7)") (class "Default")
      (node (ref "ULN1") (pin "7") (pinfunction "IN7_7") (pintype "input+no_connect"))
    )
    (net (code "107") (name "unconnected-(ULN1-OUT2-Pad15)") (class "Default")
      (node (ref "ULN1") (pin "15") (pinfunction "OUT2_15") (pintype "open_collector+no_connect"))
    )
    (net (code "108") (name "unconnected-(ULN1-OUT3-Pad14)") (class "Default")
      (node (ref "ULN1") (pin "14") (pinfunction "OUT3_14") (pintype "open_collector+no_connect"))
    )
    (net (code "109") (name "unconnected-(ULN1-OUT4-Pad13)") (class "Default")
      (node (ref "ULN1") (pin "13") (pinfunction "OUT4_13") (pintype "open_collector+no_connect"))
    )
    (net (code "110") (name "unconnected-(ULN1-OUT5-Pad12)") (class "Default")
      (node (ref "ULN1") (pin "12") (pinfunction "OUT5_12") (pintype "open_collector+no_connect"))
    )
    (net (code "111") (name "unconnected-(ULN1-OUT6-Pad11)") (class "Default")
      (node (ref "ULN1") (pin "11") (pinfunction "OUT6_11") (pintype "open_collector+no_connect"))
    )
    (net (code "112") (name "unconnected-(ULN1-OUT7-Pad10)") (class "Default")
      (node (ref "ULN1") (pin "10") (pinfunction "OUT7_10") (pintype "open_collector+no_connect"))
    )
  )
)
